# M8340X.net
KiCad netlist of a schematic drawn in EAGLE
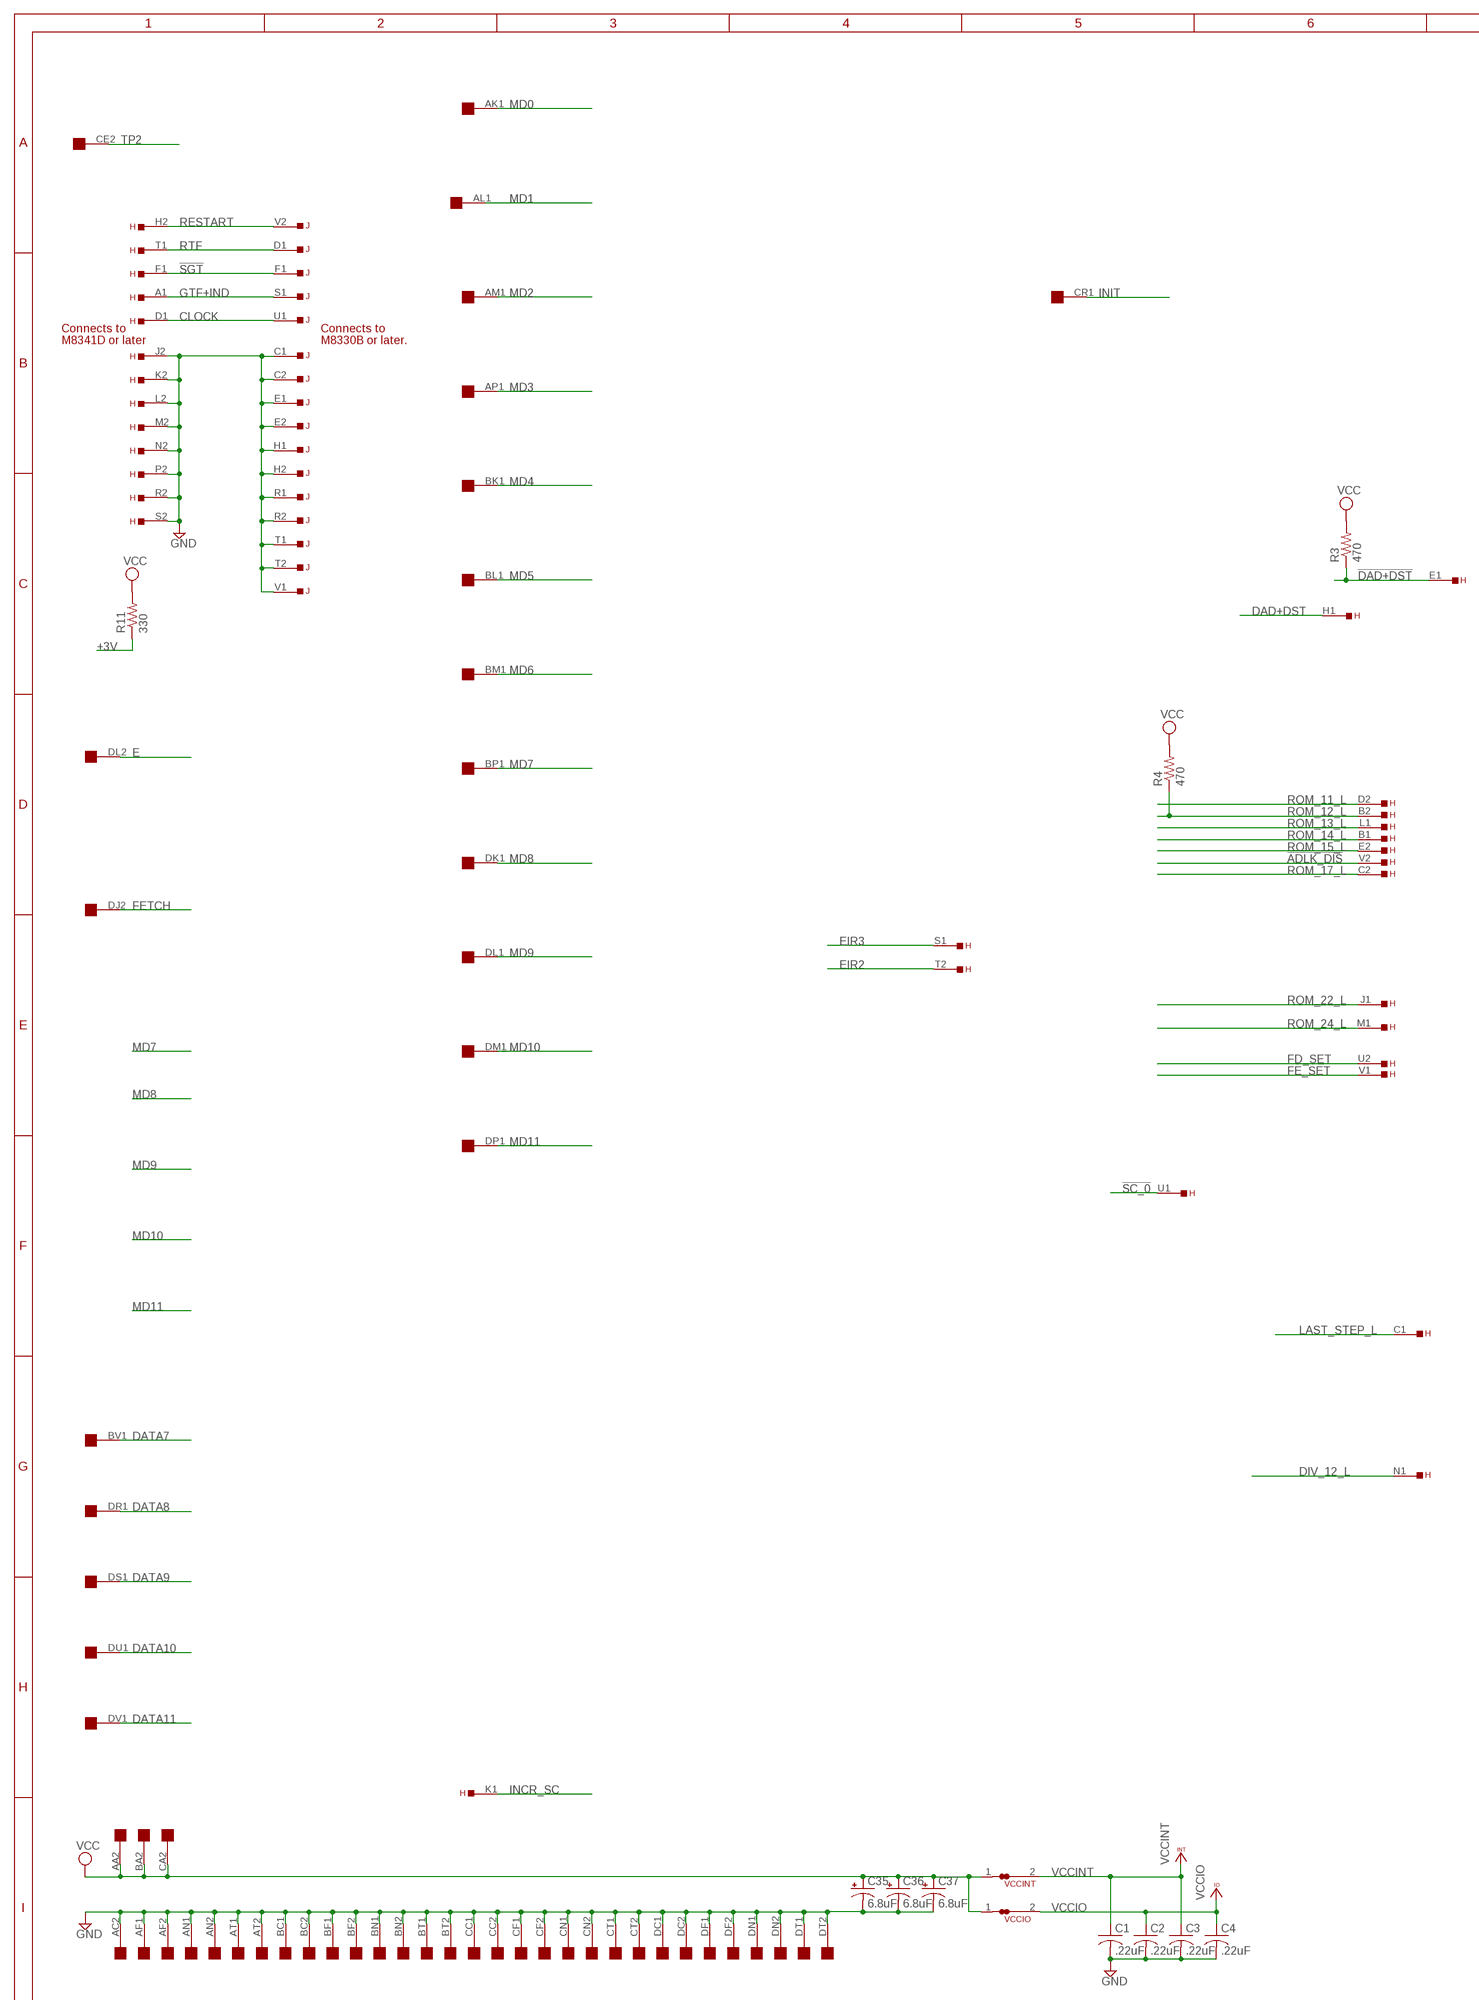
[diagram p0: schematic, sheet 1, part 1 of 2]
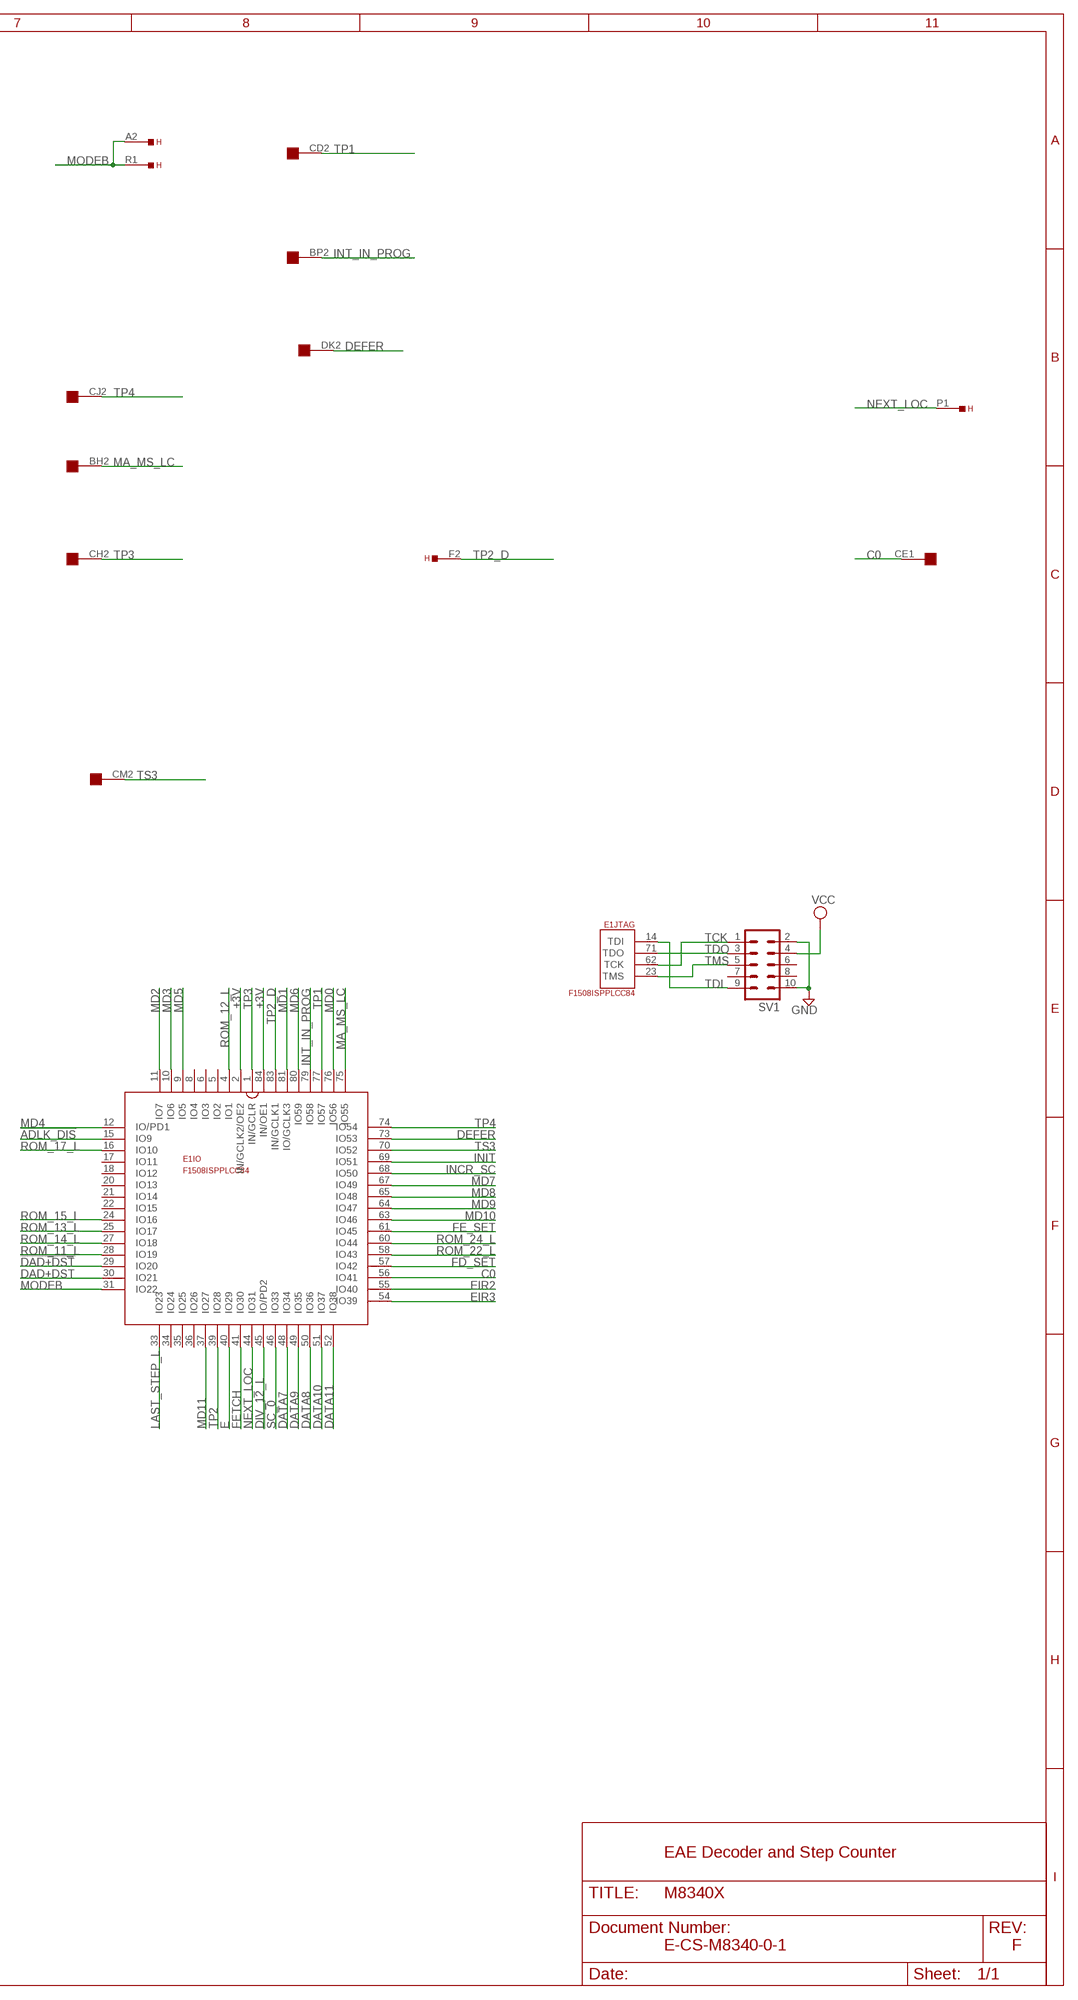
[diagram p1: schematic, sheet 1, part 2 of 2]

(export (version "E")
  (design (tool "Eeschema 10.0.6"))
  (components
    (comp (ref "C1")
      (value ".22uF")
      (footprint "eagle-import:C063-025X075")
      (libsource (lib "eagle-import") (part "C-US"))
    )
    (comp (ref "C2")
      (value ".22uF")
      (footprint "eagle-import:C063-025X075")
      (libsource (lib "eagle-import") (part "C-US"))
    )
    (comp (ref "C3")
      (value ".22uF")
      (footprint "eagle-import:C063-025X075")
      (libsource (lib "eagle-import") (part "C-US"))
    )
    (comp (ref "C4")
      (value ".22uF")
      (footprint "eagle-import:C063-025X075")
      (libsource (lib "eagle-import") (part "C-US"))
    )
    (comp (ref "C35")
      (value "6.8uF")
      (footprint "eagle-import:E12-8")
      (libsource (lib "eagle-import") (part "CPOL-USE20-8AXIAL"))
    )
    (comp (ref "C36")
      (value "6.8uF")
      (footprint "eagle-import:E12-8")
      (libsource (lib "eagle-import") (part "CPOL-USE20-8AXIAL"))
    )
    (comp (ref "C37")
      (value "6.8uF")
      (footprint "eagle-import:E12-8")
      (libsource (lib "eagle-import") (part "CPOL-USE20-8AXIAL"))
    )
    (comp (ref "E1")
      (value "F1508ISPPLCC84")
      (footprint "eagle-import:S84")
      (libsource (lib "eagle-import") (part "ATF150X84"))
    )
    (comp (ref "H")
      (value "EDGE-TOP")
      (footprint "eagle-import:EDGE-CON2")
      (libsource (lib "eagle-import") (part "EDGE-TOP"))
    )
    (comp (ref "J")
      (value "EDGE-TOP")
      (footprint "eagle-import:EDGE-CON2")
      (libsource (lib "eagle-import") (part "EDGE-TOP"))
    )
    (comp (ref "R3")
      (value "470")
      (footprint "eagle-import:0207_10")
      (libsource (lib "eagle-import") (part "R-US_0207/10"))
    )
    (comp (ref "R4")
      (value "470")
      (footprint "eagle-import:0207_10")
      (libsource (lib "eagle-import") (part "R-US_0207/10"))
    )
    (comp (ref "R11")
      (value "330")
      (footprint "eagle-import:0207_10")
      (libsource (lib "eagle-import") (part "R-US_0207/10"))
    )
    (comp (ref "SV1")
      (value "ML10")
      (footprint "eagle-import:ML10")
      (libsource (lib "eagle-import") (part "ML10"))
    )
    (comp (ref "U$2")
      (value "QUAD")
      (footprint "eagle-import:EDGE-CON8")
      (libsource (lib "eagle-import") (part "QUAD"))
    )
    (comp (ref "VCCINT")
      (value "JUMPER-NC1")
      (footprint "eagle-import:NC1")
      (libsource (lib "eagle-import") (part "JUMPER-NC1"))
    )
    (comp (ref "VCCIO")
      (value "JUMPER-NC1")
      (footprint "eagle-import:NC1")
      (libsource (lib "eagle-import") (part "JUMPER-NC1"))
    )
  )
  (nets
    (net (code "1") (name "/+3V") (class "Default")
      (node (ref "E1") (pin "2") (pinfunction "IN/GCLK2/OE2_2") (pintype "input"))
      (node (ref "E1") (pin "84") (pinfunction "IN/OE1_84") (pintype "input"))
      (node (ref "R11") (pin "1") (pinfunction "1_1") (pintype "passive"))
    )
    (net (code "2") (name "/C0") (class "Default")
      (node (ref "E1") (pin "56") (pinfunction "IO41_56") (pintype "bidirectional"))
      (node (ref "U$2") (pin "CE1") (pinfunction "1_CE1") (pintype "bidirectional"))
    )
    (net (code "3") (name "/CLOCK") (class "Default")
      (node (ref "H") (pin "D1") (pinfunction "P_D1") (pintype "passive"))
      (node (ref "J") (pin "U1") (pinfunction "P_U1") (pintype "passive"))
    )
    (net (code "4") (name "/DAD+DST") (class "Default")
      (node (ref "E1") (pin "30") (pinfunction "IO21_30") (pintype "bidirectional"))
      (node (ref "H") (pin "H1") (pinfunction "P_H1") (pintype "passive"))
    )
    (net (code "5") (name "/DATA7") (class "Default")
      (node (ref "E1") (pin "48") (pinfunction "IO34_48") (pintype "bidirectional"))
      (node (ref "U$2") (pin "BV1") (pinfunction "1_BV1") (pintype "bidirectional"))
    )
    (net (code "6") (name "/DATA8") (class "Default")
      (node (ref "E1") (pin "50") (pinfunction "IO36_50") (pintype "bidirectional"))
      (node (ref "U$2") (pin "DR1") (pinfunction "1_DR1") (pintype "bidirectional"))
    )
    (net (code "7") (name "/DATA9") (class "Default")
      (node (ref "E1") (pin "49") (pinfunction "IO35_49") (pintype "bidirectional"))
      (node (ref "U$2") (pin "DS1") (pinfunction "1_DS1") (pintype "bidirectional"))
    )
    (net (code "8") (name "/DATA10") (class "Default")
      (node (ref "E1") (pin "51") (pinfunction "IO37_51") (pintype "bidirectional"))
      (node (ref "U$2") (pin "DU1") (pinfunction "1_DU1") (pintype "bidirectional"))
    )
    (net (code "9") (name "/DATA11") (class "Default")
      (node (ref "E1") (pin "52") (pinfunction "IO38_52") (pintype "bidirectional"))
      (node (ref "U$2") (pin "DV1") (pinfunction "1_DV1") (pintype "bidirectional"))
    )
    (net (code "10") (name "/DEFER") (class "Default")
      (node (ref "E1") (pin "73") (pinfunction "IO53_73") (pintype "bidirectional"))
      (node (ref "U$2") (pin "DK2") (pinfunction "1_DK2") (pintype "bidirectional"))
    )
    (net (code "11") (name "/DIV_12_L") (class "Default")
      (node (ref "E1") (pin "45") (pinfunction "IO/PD2_45") (pintype "bidirectional"))
      (node (ref "H") (pin "N1") (pinfunction "P_N1") (pintype "passive"))
    )
    (net (code "12") (name "/E") (class "Default")
      (node (ref "E1") (pin "40") (pinfunction "IO29_40") (pintype "bidirectional"))
      (node (ref "U$2") (pin "DL2") (pinfunction "1_DL2") (pintype "bidirectional"))
    )
    (net (code "13") (name "/EIR2") (class "Default")
      (node (ref "E1") (pin "55") (pinfunction "IO40_55") (pintype "bidirectional"))
      (node (ref "H") (pin "T2") (pinfunction "P_T2") (pintype "passive"))
    )
    (net (code "14") (name "/EIR3") (class "Default")
      (node (ref "E1") (pin "54") (pinfunction "IO39_54") (pintype "bidirectional"))
      (node (ref "H") (pin "S1") (pinfunction "P_S1") (pintype "passive"))
    )
    (net (code "15") (name "/FD_SET") (class "Default")
      (node (ref "E1") (pin "57") (pinfunction "IO42_57") (pintype "bidirectional"))
      (node (ref "H") (pin "U2") (pinfunction "P_U2") (pintype "passive"))
    )
    (net (code "16") (name "/FETCH") (class "Default")
      (node (ref "E1") (pin "41") (pinfunction "IO30_41") (pintype "bidirectional"))
      (node (ref "U$2") (pin "DJ2") (pinfunction "1_DJ2") (pintype "bidirectional"))
    )
    (net (code "17") (name "/FE_SET") (class "Default")
      (node (ref "E1") (pin "61") (pinfunction "IO45_61") (pintype "bidirectional"))
      (node (ref "H") (pin "V1") (pinfunction "P_V1") (pintype "passive"))
    )
    (net (code "18") (name "/GTF+IND") (class "Default")
      (node (ref "H") (pin "A1") (pinfunction "P_A1") (pintype "passive"))
      (node (ref "J") (pin "S1") (pinfunction "P_S1") (pintype "passive"))
    )
    (net (code "19") (name "/INCR_SC") (class "Default")
      (node (ref "E1") (pin "68") (pinfunction "IO50_68") (pintype "bidirectional"))
      (node (ref "H") (pin "K1") (pinfunction "P_K1") (pintype "passive"))
    )
    (net (code "20") (name "/INIT") (class "Default")
      (node (ref "E1") (pin "69") (pinfunction "IO51_69") (pintype "bidirectional"))
      (node (ref "U$2") (pin "CR1") (pinfunction "1_CR1") (pintype "bidirectional"))
    )
    (net (code "21") (name "/INT_IN_PROG") (class "Default")
      (node (ref "E1") (pin "79") (pinfunction "IO58_79") (pintype "bidirectional"))
      (node (ref "U$2") (pin "BP2") (pinfunction "1_BP2") (pintype "bidirectional"))
    )
    (net (code "22") (name "/LAST_STEP_L") (class "Default")
      (node (ref "E1") (pin "33") (pinfunction "IO23_33") (pintype "bidirectional"))
      (node (ref "H") (pin "C1") (pinfunction "P_C1") (pintype "passive"))
    )
    (net (code "23") (name "/MA_MS_LC") (class "Default")
      (node (ref "E1") (pin "75") (pinfunction "IO55_75") (pintype "bidirectional"))
      (node (ref "U$2") (pin "BH2") (pinfunction "1_BH2") (pintype "bidirectional"))
    )
    (net (code "24") (name "/MD0") (class "Default")
      (node (ref "E1") (pin "76") (pinfunction "IO56_76") (pintype "bidirectional"))
      (node (ref "U$2") (pin "AK1") (pinfunction "1_AK1") (pintype "bidirectional"))
    )
    (net (code "25") (name "/MD1") (class "Default")
      (node (ref "E1") (pin "81") (pinfunction "IO/GCLK3_81") (pintype "bidirectional"))
      (node (ref "U$2") (pin "AL1") (pinfunction "1_AL1") (pintype "bidirectional"))
    )
    (net (code "26") (name "/MD2") (class "Default")
      (node (ref "E1") (pin "11") (pinfunction "IO7_11") (pintype "bidirectional"))
      (node (ref "U$2") (pin "AM1") (pinfunction "1_AM1") (pintype "bidirectional"))
    )
    (net (code "27") (name "/MD3") (class "Default")
      (node (ref "E1") (pin "10") (pinfunction "IO6_10") (pintype "bidirectional"))
      (node (ref "U$2") (pin "AP1") (pinfunction "1_AP1") (pintype "bidirectional"))
    )
    (net (code "28") (name "/MD4") (class "Default")
      (node (ref "E1") (pin "12") (pinfunction "IO/PD1_12") (pintype "bidirectional"))
      (node (ref "U$2") (pin "BK1") (pinfunction "1_BK1") (pintype "bidirectional"))
    )
    (net (code "29") (name "/MD5") (class "Default")
      (node (ref "E1") (pin "9") (pinfunction "IO5_9") (pintype "bidirectional"))
      (node (ref "U$2") (pin "BL1") (pinfunction "1_BL1") (pintype "bidirectional"))
    )
    (net (code "30") (name "/MD6") (class "Default")
      (node (ref "E1") (pin "80") (pinfunction "IO59_80") (pintype "bidirectional"))
      (node (ref "U$2") (pin "BM1") (pinfunction "1_BM1") (pintype "bidirectional"))
    )
    (net (code "31") (name "/MD7") (class "Default")
      (node (ref "E1") (pin "67") (pinfunction "IO49_67") (pintype "bidirectional"))
      (node (ref "U$2") (pin "BP1") (pinfunction "1_BP1") (pintype "bidirectional"))
    )
    (net (code "32") (name "/MD8") (class "Default")
      (node (ref "E1") (pin "65") (pinfunction "IO48_65") (pintype "bidirectional"))
      (node (ref "U$2") (pin "DK1") (pinfunction "1_DK1") (pintype "bidirectional"))
    )
    (net (code "33") (name "/MD9") (class "Default")
      (node (ref "E1") (pin "64") (pinfunction "IO47_64") (pintype "bidirectional"))
      (node (ref "U$2") (pin "DL1") (pinfunction "1_DL1") (pintype "bidirectional"))
    )
    (net (code "34") (name "/MD10") (class "Default")
      (node (ref "E1") (pin "63") (pinfunction "IO46_63") (pintype "bidirectional"))
      (node (ref "U$2") (pin "DM1") (pinfunction "1_DM1") (pintype "bidirectional"))
    )
    (net (code "35") (name "/MD11") (class "Default")
      (node (ref "E1") (pin "37") (pinfunction "IO27_37") (pintype "bidirectional"))
      (node (ref "U$2") (pin "DP1") (pinfunction "1_DP1") (pintype "bidirectional"))
    )
    (net (code "36") (name "/MODEB") (class "Default")
      (node (ref "E1") (pin "31") (pinfunction "IO22_31") (pintype "bidirectional"))
      (node (ref "H") (pin "A2") (pinfunction "P_A2") (pintype "passive"))
      (node (ref "H") (pin "R1") (pinfunction "P_R1") (pintype "passive"))
    )
    (net (code "37") (name "/NEXT_LOC") (class "Default")
      (node (ref "E1") (pin "44") (pinfunction "IO31_44") (pintype "bidirectional"))
      (node (ref "H") (pin "P1") (pinfunction "P_P1") (pintype "passive"))
    )
    (net (code "38") (name "/RESTART") (class "Default")
      (node (ref "H") (pin "H2") (pinfunction "P_H2") (pintype "passive"))
      (node (ref "J") (pin "V2") (pinfunction "P_V2") (pintype "passive"))
    )
    (net (code "39") (name "/ROM_11_L") (class "Default")
      (node (ref "E1") (pin "28") (pinfunction "IO19_28") (pintype "bidirectional"))
      (node (ref "H") (pin "D2") (pinfunction "P_D2") (pintype "passive"))
    )
    (net (code "40") (name "/ROM_12_L") (class "Default")
      (node (ref "E1") (pin "4") (pinfunction "IO1_4") (pintype "bidirectional"))
      (node (ref "H") (pin "B2") (pinfunction "P_B2") (pintype "passive"))
      (node (ref "R4") (pin "1") (pinfunction "1_1") (pintype "passive"))
    )
    (net (code "41") (name "/ROM_13_L") (class "Default")
      (node (ref "E1") (pin "25") (pinfunction "IO17_25") (pintype "bidirectional"))
      (node (ref "H") (pin "L1") (pinfunction "P_L1") (pintype "passive"))
    )
    (net (code "42") (name "/ROM_14_L") (class "Default")
      (node (ref "E1") (pin "27") (pinfunction "IO18_27") (pintype "bidirectional"))
      (node (ref "H") (pin "B1") (pinfunction "P_B1") (pintype "passive"))
    )
    (net (code "43") (name "/ROM_15_L") (class "Default")
      (node (ref "E1") (pin "24") (pinfunction "IO16_24") (pintype "bidirectional"))
      (node (ref "H") (pin "E2") (pinfunction "P_E2") (pintype "passive"))
    )
    (net (code "44") (name "/ROM_17_L") (class "Default")
      (node (ref "E1") (pin "16") (pinfunction "IO10_16") (pintype "bidirectional"))
      (node (ref "H") (pin "C2") (pinfunction "P_C2") (pintype "passive"))
    )
    (net (code "45") (name "/ROM_22_L") (class "Default")
      (node (ref "E1") (pin "58") (pinfunction "IO43_58") (pintype "bidirectional"))
      (node (ref "H") (pin "J1") (pinfunction "P_J1") (pintype "passive"))
    )
    (net (code "46") (name "/ROM_24_L") (class "Default")
      (node (ref "E1") (pin "60") (pinfunction "IO44_60") (pintype "bidirectional"))
      (node (ref "H") (pin "M1") (pinfunction "P_M1") (pintype "passive"))
    )
    (net (code "47") (name "/RTF") (class "Default")
      (node (ref "H") (pin "T1") (pinfunction "P_T1") (pintype "passive"))
      (node (ref "J") (pin "D1") (pinfunction "P_D1") (pintype "passive"))
    )
    (net (code "48") (name "/TCK") (class "Default")
      (node (ref "E1") (pin "62") (pinfunction "TCK_62") (pintype "bidirectional"))
      (node (ref "SV1") (pin "1") (pinfunction "1_1") (pintype "passive"))
    )
    (net (code "49") (name "/TDI") (class "Default")
      (node (ref "E1") (pin "14") (pinfunction "TDI_14") (pintype "bidirectional"))
      (node (ref "SV1") (pin "9") (pinfunction "9_9") (pintype "passive"))
    )
    (net (code "50") (name "/TDO") (class "Default")
      (node (ref "E1") (pin "71") (pinfunction "TDO_71") (pintype "bidirectional"))
      (node (ref "SV1") (pin "3") (pinfunction "3_3") (pintype "passive"))
    )
    (net (code "51") (name "/TMS") (class "Default")
      (node (ref "E1") (pin "23") (pinfunction "TMS_23") (pintype "bidirectional"))
      (node (ref "SV1") (pin "5") (pinfunction "5_5") (pintype "passive"))
    )
    (net (code "52") (name "/TP1") (class "Default")
      (node (ref "E1") (pin "77") (pinfunction "IO57_77") (pintype "bidirectional"))
      (node (ref "U$2") (pin "CD2") (pinfunction "1_CD2") (pintype "bidirectional"))
    )
    (net (code "53") (name "/TP2") (class "Default")
      (node (ref "E1") (pin "39") (pinfunction "IO28_39") (pintype "bidirectional"))
      (node (ref "U$2") (pin "CE2") (pinfunction "1_CE2") (pintype "bidirectional"))
    )
    (net (code "54") (name "/TP2_D") (class "Default")
      (node (ref "E1") (pin "83") (pinfunction "IN/GCLK1_83") (pintype "input"))
      (node (ref "H") (pin "F2") (pinfunction "P_F2") (pintype "passive"))
    )
    (net (code "55") (name "/TP3") (class "Default")
      (node (ref "E1") (pin "1") (pinfunction "IN/GCLR_1") (pintype "input"))
      (node (ref "U$2") (pin "CH2") (pinfunction "1_CH2") (pintype "bidirectional"))
    )
    (net (code "56") (name "/TP4") (class "Default")
      (node (ref "E1") (pin "74") (pinfunction "IO54_74") (pintype "bidirectional"))
      (node (ref "U$2") (pin "CJ2") (pinfunction "1_CJ2") (pintype "bidirectional"))
    )
    (net (code "57") (name "/TS3") (class "Default")
      (node (ref "E1") (pin "70") (pinfunction "IO52_70") (pintype "bidirectional"))
      (node (ref "U$2") (pin "CM2") (pinfunction "1_CM2") (pintype "bidirectional"))
    )
    (net (code "58") (name "/~{ADLK_DIS}") (class "Default")
      (node (ref "E1") (pin "15") (pinfunction "IO9_15") (pintype "bidirectional"))
      (node (ref "H") (pin "V2") (pinfunction "P_V2") (pintype "passive"))
    )
    (net (code "59") (name "/~{DAD+DST}") (class "Default")
      (node (ref "E1") (pin "29") (pinfunction "IO20_29") (pintype "bidirectional"))
      (node (ref "H") (pin "E1") (pinfunction "P_E1") (pintype "passive"))
      (node (ref "R3") (pin "1") (pinfunction "1_1") (pintype "passive"))
    )
    (net (code "60") (name "/~{SC_0}") (class "Default")
      (node (ref "E1") (pin "46") (pinfunction "IO33_46") (pintype "bidirectional"))
      (node (ref "H") (pin "U1") (pinfunction "P_U1") (pintype "passive"))
    )
    (net (code "61") (name "/~{SGT}") (class "Default")
      (node (ref "H") (pin "F1") (pinfunction "P_F1") (pintype "passive"))
      (node (ref "J") (pin "F1") (pinfunction "P_F1") (pintype "passive"))
    )
    (net (code "62") (name "GND") (class "Default")
      (node (ref "C1") (pin "2") (pinfunction "2_2") (pintype "passive"))
      (node (ref "C2") (pin "2") (pinfunction "2_2") (pintype "passive"))
      (node (ref "C3") (pin "2") (pinfunction "2_2") (pintype "passive"))
      (node (ref "C35") (pin "-") (pinfunction "-_-") (pintype "passive"))
      (node (ref "C36") (pin "-") (pinfunction "-_-") (pintype "passive"))
      (node (ref "C37") (pin "-") (pinfunction "-_-") (pintype "passive"))
      (node (ref "C4") (pin "2") (pinfunction "2_2") (pintype "passive"))
      (node (ref "H") (pin "J2") (pinfunction "P_J2") (pintype "passive"))
      (node (ref "H") (pin "K2") (pinfunction "P_K2") (pintype "passive"))
      (node (ref "H") (pin "L2") (pinfunction "P_L2") (pintype "passive"))
      (node (ref "H") (pin "M2") (pinfunction "P_M2") (pintype "passive"))
      (node (ref "H") (pin "N2") (pinfunction "P_N2") (pintype "passive"))
      (node (ref "H") (pin "P2") (pinfunction "P_P2") (pintype "passive"))
      (node (ref "H") (pin "R2") (pinfunction "P_R2") (pintype "passive"))
      (node (ref "H") (pin "S2") (pinfunction "P_S2") (pintype "passive"))
      (node (ref "J") (pin "C1") (pinfunction "P_C1") (pintype "passive"))
      (node (ref "J") (pin "C2") (pinfunction "P_C2") (pintype "passive"))
      (node (ref "J") (pin "E1") (pinfunction "P_E1") (pintype "passive"))
      (node (ref "J") (pin "E2") (pinfunction "P_E2") (pintype "passive"))
      (node (ref "J") (pin "H1") (pinfunction "P_H1") (pintype "passive"))
      (node (ref "J") (pin "H2") (pinfunction "P_H2") (pintype "passive"))
      (node (ref "J") (pin "R1") (pinfunction "P_R1") (pintype "passive"))
      (node (ref "J") (pin "R2") (pinfunction "P_R2") (pintype "passive"))
      (node (ref "J") (pin "T1") (pinfunction "P_T1") (pintype "passive"))
      (node (ref "J") (pin "T2") (pinfunction "P_T2") (pintype "passive"))
      (node (ref "J") (pin "V1") (pinfunction "P_V1") (pintype "passive"))
      (node (ref "SV1") (pin "10") (pinfunction "10_10") (pintype "passive"))
      (node (ref "SV1") (pin "2") (pinfunction "2_2") (pintype "passive"))
      (node (ref "U$2") (pin "AC2") (pinfunction "1_AC2") (pintype "bidirectional"))
      (node (ref "U$2") (pin "AF1") (pinfunction "1_AF1") (pintype "bidirectional"))
      (node (ref "U$2") (pin "AF2") (pinfunction "1_AF2") (pintype "bidirectional"))
      (node (ref "U$2") (pin "AN1") (pinfunction "1_AN1") (pintype "bidirectional"))
      (node (ref "U$2") (pin "AN2") (pinfunction "1_AN2") (pintype "bidirectional"))
      (node (ref "U$2") (pin "AT1") (pinfunction "1_AT1") (pintype "bidirectional"))
      (node (ref "U$2") (pin "AT2") (pinfunction "1_AT2") (pintype "bidirectional"))
      (node (ref "U$2") (pin "BC1") (pinfunction "1_BC1") (pintype "bidirectional"))
      (node (ref "U$2") (pin "BC2") (pinfunction "1_BC2") (pintype "bidirectional"))
      (node (ref "U$2") (pin "BF1") (pinfunction "1_BF1") (pintype "bidirectional"))
      (node (ref "U$2") (pin "BF2") (pinfunction "1_BF2") (pintype "bidirectional"))
      (node (ref "U$2") (pin "BN1") (pinfunction "1_BN1") (pintype "bidirectional"))
      (node (ref "U$2") (pin "BN2") (pinfunction "1_BN2") (pintype "bidirectional"))
      (node (ref "U$2") (pin "BT1") (pinfunction "1_BT1") (pintype "bidirectional"))
      (node (ref "U$2") (pin "BT2") (pinfunction "1_BT2") (pintype "bidirectional"))
      (node (ref "U$2") (pin "CC1") (pinfunction "1_CC1") (pintype "bidirectional"))
      (node (ref "U$2") (pin "CC2") (pinfunction "1_CC2") (pintype "bidirectional"))
      (node (ref "U$2") (pin "CF1") (pinfunction "1_CF1") (pintype "bidirectional"))
      (node (ref "U$2") (pin "CF2") (pinfunction "1_CF2") (pintype "bidirectional"))
      (node (ref "U$2") (pin "CN1") (pinfunction "1_CN1") (pintype "bidirectional"))
      (node (ref "U$2") (pin "CN2") (pinfunction "1_CN2") (pintype "bidirectional"))
      (node (ref "U$2") (pin "CT1") (pinfunction "1_CT1") (pintype "bidirectional"))
      (node (ref "U$2") (pin "CT2") (pinfunction "1_CT2") (pintype "bidirectional"))
      (node (ref "U$2") (pin "DC1") (pinfunction "1_DC1") (pintype "bidirectional"))
      (node (ref "U$2") (pin "DC2") (pinfunction "1_DC2") (pintype "bidirectional"))
      (node (ref "U$2") (pin "DF1") (pinfunction "1_DF1") (pintype "bidirectional"))
      (node (ref "U$2") (pin "DF2") (pinfunction "1_DF2") (pintype "bidirectional"))
      (node (ref "U$2") (pin "DN1") (pinfunction "1_DN1") (pintype "bidirectional"))
      (node (ref "U$2") (pin "DN2") (pinfunction "1_DN2") (pintype "bidirectional"))
      (node (ref "U$2") (pin "DT1") (pinfunction "1_DT1") (pintype "bidirectional"))
      (node (ref "U$2") (pin "DT2") (pinfunction "1_DT2") (pintype "bidirectional"))
    )
    (net (code "63") (name "VCC") (class "Default")
      (node (ref "C35") (pin "+") (pinfunction "+_+") (pintype "passive"))
      (node (ref "C36") (pin "+") (pinfunction "+_+") (pintype "passive"))
      (node (ref "C37") (pin "+") (pinfunction "+_+") (pintype "passive"))
      (node (ref "R11") (pin "2") (pinfunction "2_2") (pintype "passive"))
      (node (ref "R3") (pin "2") (pinfunction "2_2") (pintype "passive"))
      (node (ref "R4") (pin "2") (pinfunction "2_2") (pintype "passive"))
      (node (ref "SV1") (pin "4") (pinfunction "4_4") (pintype "passive"))
      (node (ref "U$2") (pin "AA2") (pinfunction "1_AA2") (pintype "bidirectional"))
      (node (ref "U$2") (pin "BA2") (pinfunction "1_BA2") (pintype "bidirectional"))
      (node (ref "U$2") (pin "CA2") (pinfunction "1_CA2") (pintype "bidirectional"))
      (node (ref "VCCINT") (pin "1") (pinfunction "1_1") (pintype "bidirectional"))
      (node (ref "VCCIO") (pin "1") (pinfunction "1_1") (pintype "bidirectional"))
    )
    (net (code "64") (name "VCCINT") (class "Default")
      (node (ref "C1") (pin "1") (pinfunction "1_1") (pintype "passive"))
      (node (ref "C3") (pin "1") (pinfunction "1_1") (pintype "passive"))
      (node (ref "VCCINT") (pin "2") (pinfunction "2_2") (pintype "bidirectional"))
    )
    (net (code "65") (name "VCCIO") (class "Default")
      (node (ref "C2") (pin "1") (pinfunction "1_1") (pintype "passive"))
      (node (ref "C4") (pin "1") (pinfunction "1_1") (pintype "passive"))
      (node (ref "VCCIO") (pin "2") (pinfunction "2_2") (pintype "bidirectional"))
    )
    (net (code "66") (name "unconnected-(E1Q-IO2-Pad5)") (class "Default")
      (node (ref "E1") (pin "5") (pinfunction "IO2_5") (pintype "bidirectional"))
    )
    (net (code "67") (name "unconnected-(E1Q-IO3-Pad6)") (class "Default")
      (node (ref "E1") (pin "6") (pinfunction "IO3_6") (pintype "bidirectional"))
    )
    (net (code "68") (name "unconnected-(E1Q-IO4-Pad8)") (class "Default")
      (node (ref "E1") (pin "8") (pinfunction "IO4_8") (pintype "bidirectional"))
    )
    (net (code "69") (name "unconnected-(E1Q-IO11-Pad17)") (class "Default")
      (node (ref "E1") (pin "17") (pinfunction "IO11_17") (pintype "bidirectional"))
    )
    (net (code "70") (name "unconnected-(E1Q-IO12-Pad18)") (class "Default")
      (node (ref "E1") (pin "18") (pinfunction "IO12_18") (pintype "bidirectional"))
    )
    (net (code "71") (name "unconnected-(E1Q-IO13-Pad20)") (class "Default")
      (node (ref "E1") (pin "20") (pinfunction "IO13_20") (pintype "bidirectional"))
    )
    (net (code "72") (name "unconnected-(E1Q-IO14-Pad21)") (class "Default")
      (node (ref "E1") (pin "21") (pinfunction "IO14_21") (pintype "bidirectional"))
    )
    (net (code "73") (name "unconnected-(E1Q-IO15-Pad22)") (class "Default")
      (node (ref "E1") (pin "22") (pinfunction "IO15_22") (pintype "bidirectional"))
    )
    (net (code "74") (name "unconnected-(E1Q-IO24-Pad34)") (class "Default")
      (node (ref "E1") (pin "34") (pinfunction "IO24_34") (pintype "bidirectional"))
    )
    (net (code "75") (name "unconnected-(E1Q-IO25-Pad35)") (class "Default")
      (node (ref "E1") (pin "35") (pinfunction "IO25_35") (pintype "bidirectional"))
    )
    (net (code "76") (name "unconnected-(E1Q-IO26-Pad36)") (class "Default")
      (node (ref "E1") (pin "36") (pinfunction "IO26_36") (pintype "bidirectional"))
    )
    (net (code "77") (name "unconnected-(SV1-Pad6)") (class "Default")
      (node (ref "SV1") (pin "6") (pinfunction "6_6") (pintype "passive"))
    )
    (net (code "78") (name "unconnected-(SV1-Pad7)") (class "Default")
      (node (ref "SV1") (pin "7") (pinfunction "7_7") (pintype "passive"))
    )
    (net (code "79") (name "unconnected-(SV1-Pad8)") (class "Default")
      (node (ref "SV1") (pin "8") (pinfunction "8_8") (pintype "passive"))
    )
  )
)
